# SkematikShieldNPKver3.net
KiCad netlist of a schematic drawn in EAGLE
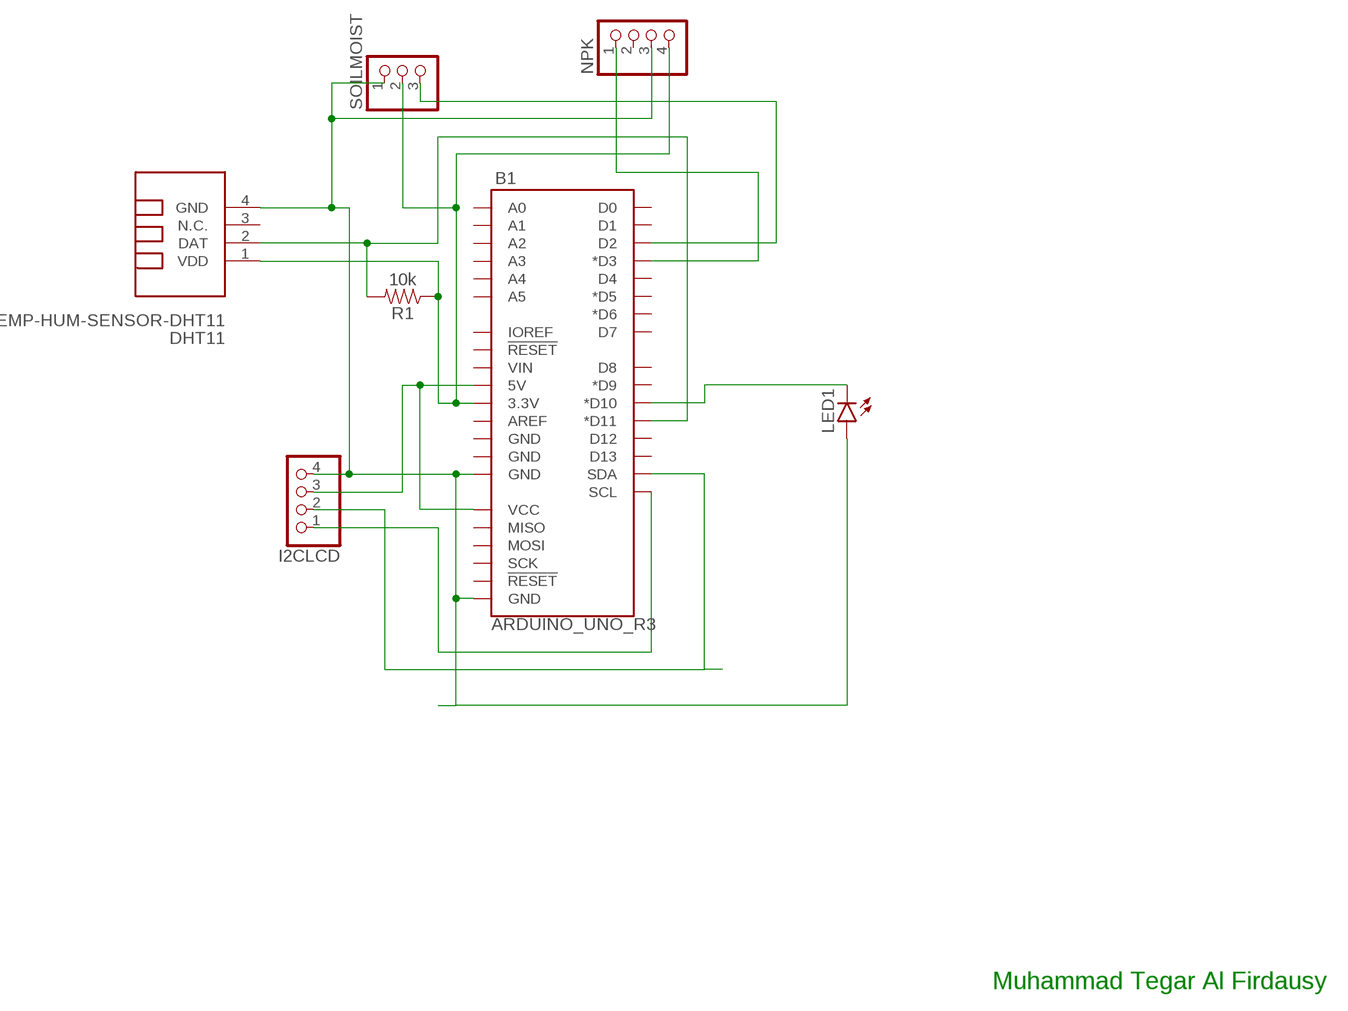
[diagram p0: schematic, sheet 1]

(export (version "E")
  (design (tool "Eeschema 10.0.6"))
  (components
    (comp (ref "B1")
      (value "ARDUINO_UNO_R3")
      (footprint "eagle-import:ARDUINO_R3")
      (libsource (lib "eagle-import") (part "ARDUINO_UNO_R3"))
    )
    (comp (ref "DHT11")
      (value "TEMP-HUM-SENSOR-DHT11")
      (footprint "eagle-import:TEMP-HUM-SENSOR-DHT11")
      (libsource (lib "eagle-import") (part "TEMP-HUM-SENSOR-DHT11"))
    )
    (comp (ref "I2CLCD")
      (value "PINHD-1X4")
      (footprint "eagle-import:1X04")
      (libsource (lib "eagle-import") (part "PINHD-1X4"))
    )
    (comp (ref "LED1")
      (value "LED5MM")
      (footprint "eagle-import:LED5MM")
      (libsource (lib "eagle-import") (part "LED5MM"))
    )
    (comp (ref "NPK")
      (value "PINHD-1X4")
      (footprint "eagle-import:1X04")
      (libsource (lib "eagle-import") (part "PINHD-1X4"))
    )
    (comp (ref "R1")
      (value "10k")
      (footprint "eagle-import:AXIAL-0.3")
      (libsource (lib "eagle-import") (part "10KOHM-HORIZ-1/4W-1%"))
    )
    (comp (ref "SOILMOIST")
      (value "PINHD-1X3")
      (footprint "eagle-import:1X03")
      (libsource (lib "eagle-import") (part "PINHD-1X3"))
    )
  )
  (nets
    (net (code "1") (name "Net-(B1-*D3)") (class "Default")
      (node (ref "B1") (pin "D3") (pinfunction "*D3_D3") (pintype "bidirectional"))
      (node (ref "NPK") (pin "1") (pinfunction "1_1") (pintype "passive"))
    )
    (net (code "2") (name "Net-(B1-*D10)") (class "Default")
      (node (ref "B1") (pin "D10") (pinfunction "*D10_D10") (pintype "bidirectional"))
      (node (ref "LED1") (pin "K") (pinfunction "C_K") (pintype "passive"))
    )
    (net (code "3") (name "Net-(B1-*D11)") (class "Default")
      (node (ref "B1") (pin "D11") (pinfunction "*D11_D11") (pintype "bidirectional"))
      (node (ref "DHT11") (pin "2") (pinfunction "DAT_2") (pintype "bidirectional"))
      (node (ref "R1") (pin "P$2") (pinfunction "2_P$2") (pintype "passive"))
    )
    (net (code "4") (name "Net-(B1-Pad5V)") (class "Default")
      (node (ref "B1") (pin "5V") (pinfunction "5V_5V") (pintype "bidirectional"))
      (node (ref "B1") (pin "VCC") (pinfunction "VCC_VCC") (pintype "bidirectional"))
      (node (ref "I2CLCD") (pin "3") (pinfunction "3_3") (pintype "passive"))
    )
    (net (code "5") (name "Net-(B1-PadD2)") (class "Default")
      (node (ref "B1") (pin "D2") (pinfunction "D2_D2") (pintype "bidirectional"))
      (node (ref "SOILMOIST") (pin "3") (pinfunction "3_3") (pintype "passive"))
    )
    (net (code "6") (name "Net-(B1-PadSCL)") (class "Default")
      (node (ref "B1") (pin "SCL") (pinfunction "SCL_SCL") (pintype "bidirectional"))
      (node (ref "I2CLCD") (pin "1") (pinfunction "1_1") (pintype "passive"))
    )
    (net (code "7") (name "Net-(B1-PadSDA)") (class "Default")
      (node (ref "B1") (pin "SDA") (pinfunction "SDA_SDA") (pintype "bidirectional"))
      (node (ref "I2CLCD") (pin "2") (pinfunction "2_2") (pintype "passive"))
    )
    (net (code "8") (name "Net-(DHT11-GND)") (class "Default")
      (node (ref "B1") (pin "GND@1") (pinfunction "GND_GND@1") (pintype "bidirectional"))
      (node (ref "B1") (pin "GND@2") (pinfunction "GND_GND@2") (pintype "bidirectional"))
      (node (ref "DHT11") (pin "4") (pinfunction "GND_4") (pintype "power_in"))
      (node (ref "I2CLCD") (pin "4") (pinfunction "4_4") (pintype "passive"))
      (node (ref "LED1") (pin "A") (pinfunction "A_A") (pintype "passive"))
      (node (ref "NPK") (pin "3") (pinfunction "3_3") (pintype "passive"))
      (node (ref "SOILMOIST") (pin "1") (pinfunction "1_1") (pintype "passive"))
    )
    (net (code "9") (name "Net-(DHT11-VDD)") (class "Default")
      (node (ref "B1") (pin "3.3V") (pinfunction "3.3V_3.3V") (pintype "bidirectional"))
      (node (ref "DHT11") (pin "1") (pinfunction "VDD_1") (pintype "power_in"))
      (node (ref "NPK") (pin "4") (pinfunction "4_4") (pintype "passive"))
      (node (ref "R1") (pin "P$1") (pinfunction "1_P$1") (pintype "passive"))
      (node (ref "SOILMOIST") (pin "2") (pinfunction "2_2") (pintype "passive"))
    )
    (net (code "10") (name "unconnected-(B1-*D5-PadD5)") (class "Default")
      (node (ref "B1") (pin "D5") (pinfunction "*D5_D5") (pintype "bidirectional"))
    )
    (net (code "11") (name "unconnected-(B1-*D6-PadD6)") (class "Default")
      (node (ref "B1") (pin "D6") (pinfunction "*D6_D6") (pintype "bidirectional"))
    )
    (net (code "12") (name "unconnected-(B1-*D9-PadD9)") (class "Default")
      (node (ref "B1") (pin "D9") (pinfunction "*D9_D9") (pintype "bidirectional"))
    )
    (net (code "13") (name "unconnected-(B1-GND-PadGND@3)") (class "Default")
      (node (ref "B1") (pin "GND@3") (pinfunction "GND_GND@3") (pintype "bidirectional"))
    )
    (net (code "14") (name "unconnected-(B1-GND-PadGND@4)") (class "Default")
      (node (ref "B1") (pin "GND@4") (pinfunction "GND_GND@4") (pintype "bidirectional"))
    )
    (net (code "15") (name "unconnected-(B1-PadA0)") (class "Default")
      (node (ref "B1") (pin "A0") (pinfunction "A0_A0") (pintype "bidirectional"))
    )
    (net (code "16") (name "unconnected-(B1-PadA1)") (class "Default")
      (node (ref "B1") (pin "A1") (pinfunction "A1_A1") (pintype "bidirectional"))
    )
    (net (code "17") (name "unconnected-(B1-PadA2)") (class "Default")
      (node (ref "B1") (pin "A2") (pinfunction "A2_A2") (pintype "bidirectional"))
    )
    (net (code "18") (name "unconnected-(B1-PadA3)") (class "Default")
      (node (ref "B1") (pin "A3") (pinfunction "A3_A3") (pintype "bidirectional"))
    )
    (net (code "19") (name "unconnected-(B1-PadA4)") (class "Default")
      (node (ref "B1") (pin "A4") (pinfunction "A4_A4") (pintype "bidirectional"))
    )
    (net (code "20") (name "unconnected-(B1-PadA5)") (class "Default")
      (node (ref "B1") (pin "A5") (pinfunction "A5_A5") (pintype "bidirectional"))
    )
    (net (code "21") (name "unconnected-(B1-PadAREF)") (class "Default")
      (node (ref "B1") (pin "AREF") (pinfunction "AREF_AREF") (pintype "bidirectional"))
    )
    (net (code "22") (name "unconnected-(B1-PadD0)") (class "Default")
      (node (ref "B1") (pin "D0") (pinfunction "D0_D0") (pintype "bidirectional"))
    )
    (net (code "23") (name "unconnected-(B1-PadD1)") (class "Default")
      (node (ref "B1") (pin "D1") (pinfunction "D1_D1") (pintype "bidirectional"))
    )
    (net (code "24") (name "unconnected-(B1-PadD4)") (class "Default")
      (node (ref "B1") (pin "D4") (pinfunction "D4_D4") (pintype "bidirectional"))
    )
    (net (code "25") (name "unconnected-(B1-PadD7)") (class "Default")
      (node (ref "B1") (pin "D7") (pinfunction "D7_D7") (pintype "bidirectional"))
    )
    (net (code "26") (name "unconnected-(B1-PadD8)") (class "Default")
      (node (ref "B1") (pin "D8") (pinfunction "D8_D8") (pintype "bidirectional"))
    )
    (net (code "27") (name "unconnected-(B1-PadD12)") (class "Default")
      (node (ref "B1") (pin "D12") (pinfunction "D12_D12") (pintype "bidirectional"))
    )
    (net (code "28") (name "unconnected-(B1-PadD13)") (class "Default")
      (node (ref "B1") (pin "D13") (pinfunction "D13_D13") (pintype "bidirectional"))
    )
    (net (code "29") (name "unconnected-(B1-PadIOREF)") (class "Default")
      (node (ref "B1") (pin "IOREF") (pinfunction "IOREF_IOREF") (pintype "bidirectional"))
    )
    (net (code "30") (name "unconnected-(B1-PadMISO)") (class "Default")
      (node (ref "B1") (pin "MISO") (pinfunction "MISO_MISO") (pintype "bidirectional"))
    )
    (net (code "31") (name "unconnected-(B1-PadMOSI)") (class "Default")
      (node (ref "B1") (pin "MOSI") (pinfunction "MOSI_MOSI") (pintype "bidirectional"))
    )
    (net (code "32") (name "unconnected-(B1-PadSCK)") (class "Default")
      (node (ref "B1") (pin "SCK") (pinfunction "SCK_SCK") (pintype "bidirectional"))
    )
    (net (code "33") (name "unconnected-(B1-PadVIN)") (class "Default")
      (node (ref "B1") (pin "VIN") (pinfunction "VIN_VIN") (pintype "bidirectional"))
    )
    (net (code "34") (name "unconnected-(B1-~{RESET}-PadRESET@1)") (class "Default")
      (node (ref "B1") (pin "RESET@1") (pinfunction "~{RESET}_RESET@1") (pintype "bidirectional"))
    )
    (net (code "35") (name "unconnected-(B1-~{RESET}-PadRESET@2)") (class "Default")
      (node (ref "B1") (pin "RESET@2") (pinfunction "~{RESET}_RESET@2") (pintype "bidirectional"))
    )
    (net (code "36") (name "unconnected-(DHT11-N.C.-Pad3)") (class "Default")
      (node (ref "DHT11") (pin "3") (pinfunction "N.C._3") (pintype "passive"))
    )
    (net (code "37") (name "unconnected-(NPK-Pad2)") (class "Default")
      (node (ref "NPK") (pin "2") (pinfunction "2_2") (pintype "passive"))
    )
  )
)
